# mosfet_board_v2.net
KiCad netlist of a schematic drawn in EAGLE
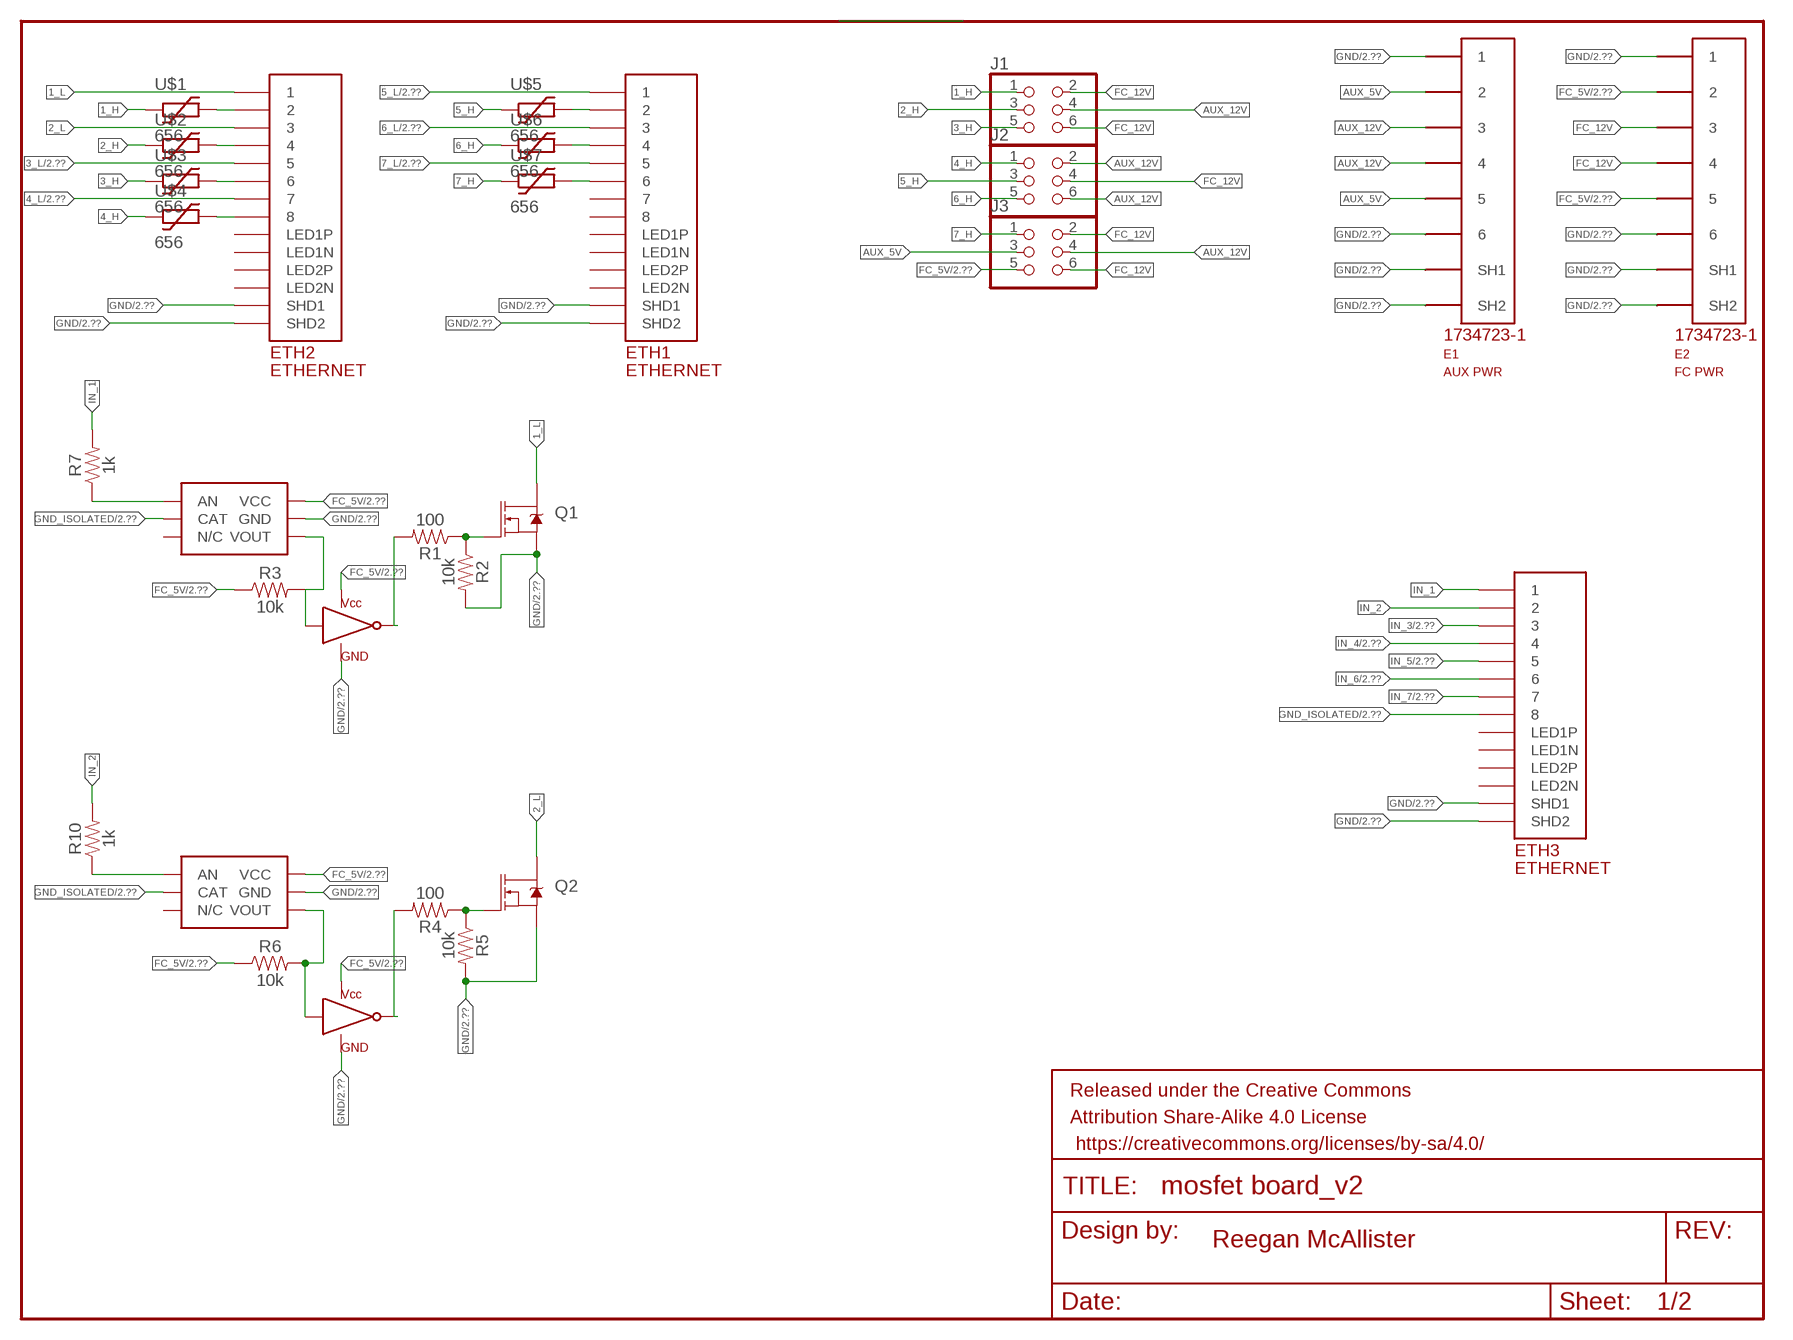
[diagram p0: schematic, sheet 1]
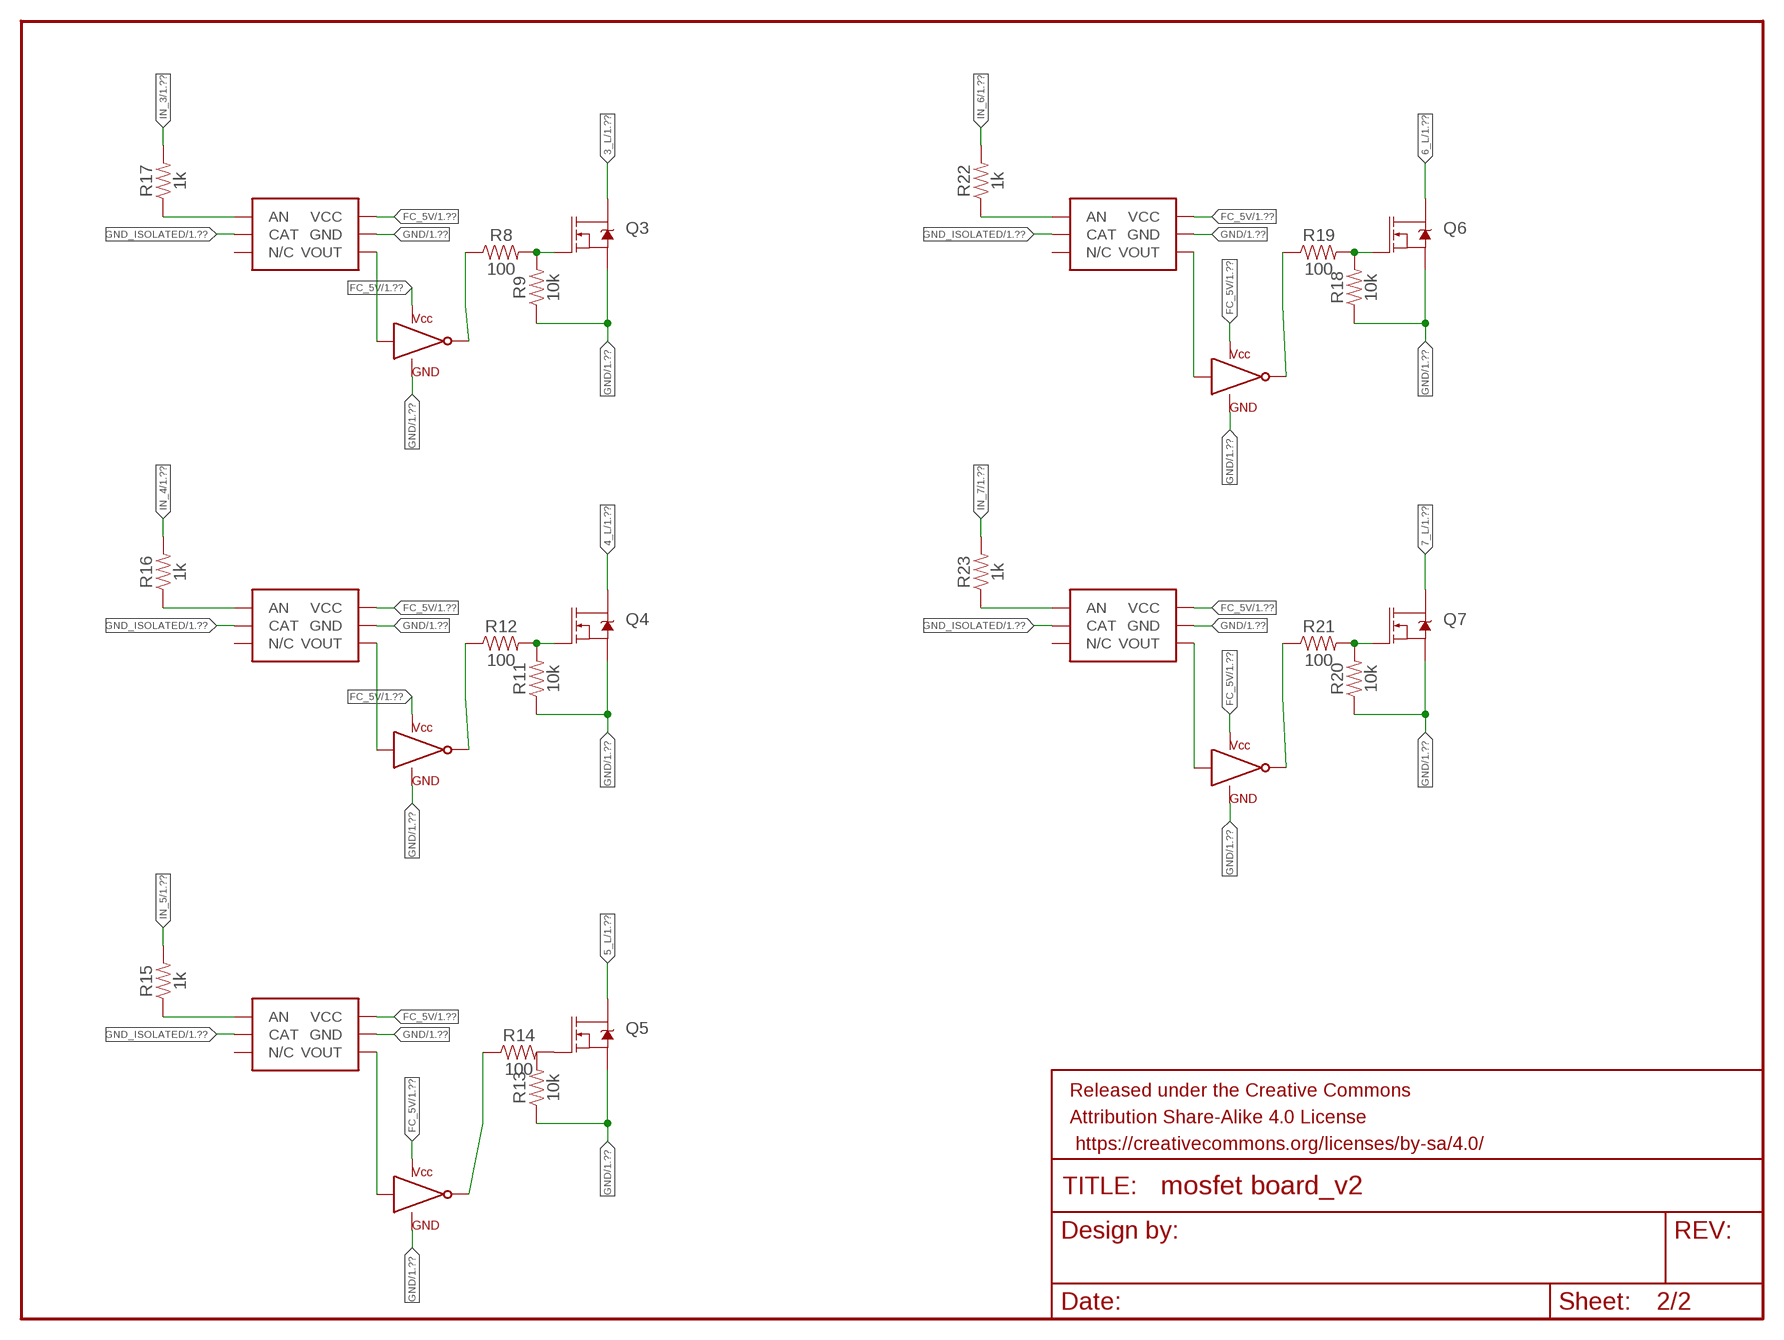
[diagram p1: schematic, sheet 2]

(export (version "E")
  (design (tool "Eeschema 10.0.6"))
  (components
    (comp (ref "E1")
      (value "AUX PWR")
      (footprint "eagle-import:1734723-1_RJ11")
      (libsource (lib "eagle-import") (part "5555140-6"))
    )
    (comp (ref "E2")
      (value "FC PWR")
      (footprint "eagle-import:1734723-1_RJ11")
      (libsource (lib "eagle-import") (part "5555140-6"))
    )
    (comp (ref "ETH1")
      (value "ETHERNET")
      (footprint "eagle-import:A122645-ND")
      (libsource (lib "eagle-import") (part "ETHERNET"))
    )
    (comp (ref "ETH2")
      (value "ETHERNET")
      (footprint "eagle-import:A122645-ND")
      (libsource (lib "eagle-import") (part "ETHERNET"))
    )
    (comp (ref "ETH3")
      (value "ETHERNET")
      (footprint "eagle-import:A122645-ND")
      (libsource (lib "eagle-import") (part "ETHERNET"))
    )
    (comp (ref "FRAME1")
      (value "FRAME-LETTERNO_PACKAGE")
      (footprint "eagle-import:DUMMY")
      (fields (field (name "DESIGNER") "Nobody"))
      (libsource (lib "eagle-import") (part "FRAME-LETTERNO_PACKAGE"))
    )
    (comp (ref "J1")
      (value "PINHD-2X3")
      (footprint "eagle-import:2X03")
      (libsource (lib "eagle-import") (part "PINHD-2X3"))
    )
    (comp (ref "J2")
      (value "PINHD-2X3")
      (footprint "eagle-import:2X03")
      (libsource (lib "eagle-import") (part "PINHD-2X3"))
    )
    (comp (ref "J3")
      (value "PINHD-2X3")
      (footprint "eagle-import:2X03")
      (libsource (lib "eagle-import") (part "PINHD-2X3"))
    )
    (comp (ref "Q1")
      (value "MOSFET-NCH-AO3404A")
      (footprint "eagle-import:SOT23-3")
      (libsource (lib "eagle-import") (part "MOSFET-NCH-AO3404A"))
    )
    (comp (ref "Q2")
      (value "MOSFET-NCH-AO3404A")
      (footprint "eagle-import:SOT23-3")
      (libsource (lib "eagle-import") (part "MOSFET-NCH-AO3404A"))
    )
    (comp (ref "R1")
      (value "100")
      (footprint "eagle-import:0805")
      (libsource (lib "eagle-import") (part "RESISTOR0805"))
    )
    (comp (ref "R2")
      (value "10k")
      (footprint "eagle-import:0805")
      (libsource (lib "eagle-import") (part "RESISTOR0805"))
    )
    (comp (ref "R3")
      (value "10k")
      (footprint "eagle-import:0805")
      (libsource (lib "eagle-import") (part "RESISTOR0805"))
    )
    (comp (ref "R4")
      (value "100")
      (footprint "eagle-import:0805")
      (libsource (lib "eagle-import") (part "RESISTOR0805"))
    )
    (comp (ref "R5")
      (value "10k")
      (footprint "eagle-import:0805")
      (libsource (lib "eagle-import") (part "RESISTOR0805"))
    )
    (comp (ref "R6")
      (value "10k")
      (footprint "eagle-import:0805")
      (libsource (lib "eagle-import") (part "RESISTOR0805"))
    )
    (comp (ref "R7")
      (value "1k")
      (footprint "eagle-import:0805")
      (libsource (lib "eagle-import") (part "RESISTOR0805"))
    )
    (comp (ref "R10")
      (value "1k")
      (footprint "eagle-import:0805")
      (libsource (lib "eagle-import") (part "RESISTOR0805"))
    )
    (comp (ref "U$1")
      (value "656")
      (footprint "eagle-import:656")
      (libsource (lib "eagle-import") (part "656"))
    )
    (comp (ref "U$2")
      (value "656")
      (footprint "eagle-import:656")
      (libsource (lib "eagle-import") (part "656"))
    )
    (comp (ref "U$3")
      (value "656")
      (footprint "eagle-import:656")
      (libsource (lib "eagle-import") (part "656"))
    )
    (comp (ref "U$4")
      (value "656")
      (footprint "eagle-import:656")
      (libsource (lib "eagle-import") (part "656"))
    )
    (comp (ref "U$5")
      (value "656")
      (footprint "eagle-import:656")
      (libsource (lib "eagle-import") (part "656"))
    )
    (comp (ref "U$6")
      (value "656")
      (footprint "eagle-import:656")
      (libsource (lib "eagle-import") (part "656"))
    )
    (comp (ref "U$7")
      (value "656")
      (footprint "eagle-import:656")
      (libsource (lib "eagle-import") (part "656"))
    )
    (comp (ref "U$8")
      (value "H11L1M")
      (footprint "eagle-import:H11L1M")
      (libsource (lib "eagle-import") (part "H11L1M"))
    )
    (comp (ref "U$9")
      (value "SN74LVC1G04-Q1")
      (footprint "eagle-import:SOT-23-5")
      (libsource (lib "eagle-import") (part "SN74LVC1G04-Q1"))
    )
    (comp (ref "U$10")
      (value "H11L1M")
      (footprint "eagle-import:H11L1M")
      (libsource (lib "eagle-import") (part "H11L1M"))
    )
    (comp (ref "U$11")
      (value "SN74LVC1G04-Q1")
      (footprint "eagle-import:SOT-23-5")
      (libsource (lib "eagle-import") (part "SN74LVC1G04-Q1"))
    )
    (comp (ref "FRAME2")
      (value "FRAME-LETTERNO_PACKAGE")
      (footprint "eagle-import:DUMMY")
      (fields (field (name "DESIGNER") "Nobody"))
      (libsource (lib "eagle-import") (part "FRAME-LETTERNO_PACKAGE"))
    )
    (comp (ref "Q3")
      (value "MOSFET-NCH-AO3404A")
      (footprint "eagle-import:SOT23-3")
      (libsource (lib "eagle-import") (part "MOSFET-NCH-AO3404A"))
    )
    (comp (ref "Q4")
      (value "MOSFET-NCH-AO3404A")
      (footprint "eagle-import:SOT23-3")
      (libsource (lib "eagle-import") (part "MOSFET-NCH-AO3404A"))
    )
    (comp (ref "Q5")
      (value "MOSFET-NCH-AO3404A")
      (footprint "eagle-import:SOT23-3")
      (libsource (lib "eagle-import") (part "MOSFET-NCH-AO3404A"))
    )
    (comp (ref "Q6")
      (value "MOSFET-NCH-AO3404A")
      (footprint "eagle-import:SOT23-3")
      (libsource (lib "eagle-import") (part "MOSFET-NCH-AO3404A"))
    )
    (comp (ref "Q7")
      (value "MOSFET-NCH-AO3404A")
      (footprint "eagle-import:SOT23-3")
      (libsource (lib "eagle-import") (part "MOSFET-NCH-AO3404A"))
    )
    (comp (ref "R8")
      (value "100")
      (footprint "eagle-import:0805")
      (libsource (lib "eagle-import") (part "RESISTOR0805"))
    )
    (comp (ref "R9")
      (value "10k")
      (footprint "eagle-import:0805")
      (libsource (lib "eagle-import") (part "RESISTOR0805"))
    )
    (comp (ref "R11")
      (value "10k")
      (footprint "eagle-import:0805")
      (libsource (lib "eagle-import") (part "RESISTOR0805"))
    )
    (comp (ref "R12")
      (value "100")
      (footprint "eagle-import:0805")
      (libsource (lib "eagle-import") (part "RESISTOR0805"))
    )
    (comp (ref "R13")
      (value "10k")
      (footprint "eagle-import:0805")
      (libsource (lib "eagle-import") (part "RESISTOR0805"))
    )
    (comp (ref "R14")
      (value "100")
      (footprint "eagle-import:0805")
      (libsource (lib "eagle-import") (part "RESISTOR0805"))
    )
    (comp (ref "R15")
      (value "1k")
      (footprint "eagle-import:0805")
      (libsource (lib "eagle-import") (part "RESISTOR0805"))
    )
    (comp (ref "R16")
      (value "1k")
      (footprint "eagle-import:0805")
      (libsource (lib "eagle-import") (part "RESISTOR0805"))
    )
    (comp (ref "R17")
      (value "1k")
      (footprint "eagle-import:0805")
      (libsource (lib "eagle-import") (part "RESISTOR0805"))
    )
    (comp (ref "R18")
      (value "10k")
      (footprint "eagle-import:0805")
      (libsource (lib "eagle-import") (part "RESISTOR0805"))
    )
    (comp (ref "R19")
      (value "100")
      (footprint "eagle-import:0805")
      (libsource (lib "eagle-import") (part "RESISTOR0805"))
    )
    (comp (ref "R20")
      (value "10k")
      (footprint "eagle-import:0805")
      (libsource (lib "eagle-import") (part "RESISTOR0805"))
    )
    (comp (ref "R21")
      (value "100")
      (footprint "eagle-import:0805")
      (libsource (lib "eagle-import") (part "RESISTOR0805"))
    )
    (comp (ref "R22")
      (value "1k")
      (footprint "eagle-import:0805")
      (libsource (lib "eagle-import") (part "RESISTOR0805"))
    )
    (comp (ref "R23")
      (value "1k")
      (footprint "eagle-import:0805")
      (libsource (lib "eagle-import") (part "RESISTOR0805"))
    )
    (comp (ref "U$12")
      (value "H11L1M")
      (footprint "eagle-import:H11L1M")
      (libsource (lib "eagle-import") (part "H11L1M"))
    )
    (comp (ref "U$13")
      (value "SN74LVC1G04-Q1")
      (footprint "eagle-import:SOT-23-5")
      (libsource (lib "eagle-import") (part "SN74LVC1G04-Q1"))
    )
    (comp (ref "U$14")
      (value "H11L1M")
      (footprint "eagle-import:H11L1M")
      (libsource (lib "eagle-import") (part "H11L1M"))
    )
    (comp (ref "U$15")
      (value "SN74LVC1G04-Q1")
      (footprint "eagle-import:SOT-23-5")
      (libsource (lib "eagle-import") (part "SN74LVC1G04-Q1"))
    )
    (comp (ref "U$16")
      (value "H11L1M")
      (footprint "eagle-import:H11L1M")
      (libsource (lib "eagle-import") (part "H11L1M"))
    )
    (comp (ref "U$17")
      (value "SN74LVC1G04-Q1")
      (footprint "eagle-import:SOT-23-5")
      (libsource (lib "eagle-import") (part "SN74LVC1G04-Q1"))
    )
    (comp (ref "U$18")
      (value "H11L1M")
      (footprint "eagle-import:H11L1M")
      (libsource (lib "eagle-import") (part "H11L1M"))
    )
    (comp (ref "U$19")
      (value "SN74LVC1G04-Q1")
      (footprint "eagle-import:SOT-23-5")
      (libsource (lib "eagle-import") (part "SN74LVC1G04-Q1"))
    )
    (comp (ref "U$20")
      (value "H11L1M")
      (footprint "eagle-import:H11L1M")
      (libsource (lib "eagle-import") (part "H11L1M"))
    )
    (comp (ref "U$21")
      (value "SN74LVC1G04-Q1")
      (footprint "eagle-import:SOT-23-5")
      (libsource (lib "eagle-import") (part "SN74LVC1G04-Q1"))
    )
  )
  (nets
    (net (code "1") (name "1_H") (class "Default")
      (node (ref "J1") (pin "1") (pinfunction "1_1") (pintype "passive"))
      (node (ref "U$1") (pin "P$1") (pinfunction "1_P$1") (pintype "passive"))
    )
    (net (code "2") (name "1_L") (class "Default")
      (node (ref "ETH2") (pin "P$1") (pinfunction "1_P$1") (pintype "bidirectional"))
      (node (ref "Q1") (pin "3") (pinfunction "D_3") (pintype "bidirectional"))
    )
    (net (code "3") (name "2_H") (class "Default")
      (node (ref "J1") (pin "3") (pinfunction "3_3") (pintype "passive"))
      (node (ref "U$2") (pin "P$1") (pinfunction "1_P$1") (pintype "passive"))
    )
    (net (code "4") (name "2_L") (class "Default")
      (node (ref "ETH2") (pin "P$3") (pinfunction "3_P$3") (pintype "bidirectional"))
      (node (ref "Q2") (pin "3") (pinfunction "D_3") (pintype "bidirectional"))
    )
    (net (code "5") (name "3_H") (class "Default")
      (node (ref "J1") (pin "5") (pinfunction "5_5") (pintype "passive"))
      (node (ref "U$3") (pin "P$1") (pinfunction "1_P$1") (pintype "passive"))
    )
    (net (code "6") (name "3_L") (class "Default")
      (node (ref "ETH2") (pin "P$5") (pinfunction "5_P$5") (pintype "bidirectional"))
      (node (ref "Q3") (pin "3") (pinfunction "D_3") (pintype "bidirectional"))
    )
    (net (code "7") (name "4_H") (class "Default")
      (node (ref "J2") (pin "1") (pinfunction "1_1") (pintype "passive"))
      (node (ref "U$4") (pin "P$1") (pinfunction "1_P$1") (pintype "passive"))
    )
    (net (code "8") (name "4_L") (class "Default")
      (node (ref "ETH2") (pin "P$7") (pinfunction "7_P$7") (pintype "bidirectional"))
      (node (ref "Q4") (pin "3") (pinfunction "D_3") (pintype "bidirectional"))
    )
    (net (code "9") (name "5_H") (class "Default")
      (node (ref "J2") (pin "3") (pinfunction "3_3") (pintype "passive"))
      (node (ref "U$5") (pin "P$1") (pinfunction "1_P$1") (pintype "passive"))
    )
    (net (code "10") (name "5_L") (class "Default")
      (node (ref "ETH1") (pin "P$1") (pinfunction "1_P$1") (pintype "bidirectional"))
      (node (ref "Q5") (pin "3") (pinfunction "D_3") (pintype "bidirectional"))
    )
    (net (code "11") (name "6_H") (class "Default")
      (node (ref "J2") (pin "5") (pinfunction "5_5") (pintype "passive"))
      (node (ref "U$6") (pin "P$1") (pinfunction "1_P$1") (pintype "passive"))
    )
    (net (code "12") (name "6_L") (class "Default")
      (node (ref "ETH1") (pin "P$3") (pinfunction "3_P$3") (pintype "bidirectional"))
      (node (ref "Q6") (pin "3") (pinfunction "D_3") (pintype "bidirectional"))
    )
    (net (code "13") (name "7_H") (class "Default")
      (node (ref "J3") (pin "1") (pinfunction "1_1") (pintype "passive"))
      (node (ref "U$7") (pin "P$1") (pinfunction "1_P$1") (pintype "passive"))
    )
    (net (code "14") (name "7_L") (class "Default")
      (node (ref "ETH1") (pin "P$5") (pinfunction "5_P$5") (pintype "bidirectional"))
      (node (ref "Q7") (pin "3") (pinfunction "D_3") (pintype "bidirectional"))
    )
    (net (code "15") (name "AUX_5V") (class "Default")
      (node (ref "E1") (pin "2") (pinfunction "2_2") (pintype "bidirectional"))
      (node (ref "E1") (pin "5") (pinfunction "5_5") (pintype "bidirectional"))
      (node (ref "J3") (pin "3") (pinfunction "3_3") (pintype "passive"))
    )
    (net (code "16") (name "AUX_12V") (class "Default")
      (node (ref "E1") (pin "3") (pinfunction "3_3") (pintype "bidirectional"))
      (node (ref "E1") (pin "4") (pinfunction "4_4") (pintype "bidirectional"))
      (node (ref "J1") (pin "4") (pinfunction "4_4") (pintype "passive"))
      (node (ref "J2") (pin "2") (pinfunction "2_2") (pintype "passive"))
      (node (ref "J2") (pin "6") (pinfunction "6_6") (pintype "passive"))
      (node (ref "J3") (pin "4") (pinfunction "4_4") (pintype "passive"))
    )
    (net (code "17") (name "FC_5V") (class "Default")
      (node (ref "E2") (pin "2") (pinfunction "2_2") (pintype "bidirectional"))
      (node (ref "E2") (pin "5") (pinfunction "5_5") (pintype "bidirectional"))
      (node (ref "J3") (pin "5") (pinfunction "5_5") (pintype "passive"))
      (node (ref "R3") (pin "1") (pinfunction "1_1") (pintype "passive"))
      (node (ref "R6") (pin "1") (pinfunction "1_1") (pintype "passive"))
      (node (ref "U$10") (pin "P$6") (pinfunction "VCC_P$6") (pintype "bidirectional"))
      (node (ref "U$11") (pin "P$5") (pinfunction "VCC_P$5") (pintype "bidirectional"))
      (node (ref "U$12") (pin "P$6") (pinfunction "VCC_P$6") (pintype "bidirectional"))
      (node (ref "U$13") (pin "P$5") (pinfunction "VCC_P$5") (pintype "bidirectional"))
      (node (ref "U$14") (pin "P$6") (pinfunction "VCC_P$6") (pintype "bidirectional"))
      (node (ref "U$15") (pin "P$5") (pinfunction "VCC_P$5") (pintype "bidirectional"))
      (node (ref "U$16") (pin "P$6") (pinfunction "VCC_P$6") (pintype "bidirectional"))
      (node (ref "U$17") (pin "P$5") (pinfunction "VCC_P$5") (pintype "bidirectional"))
      (node (ref "U$18") (pin "P$6") (pinfunction "VCC_P$6") (pintype "bidirectional"))
      (node (ref "U$19") (pin "P$5") (pinfunction "VCC_P$5") (pintype "bidirectional"))
      (node (ref "U$20") (pin "P$6") (pinfunction "VCC_P$6") (pintype "bidirectional"))
      (node (ref "U$21") (pin "P$5") (pinfunction "VCC_P$5") (pintype "bidirectional"))
      (node (ref "U$8") (pin "P$6") (pinfunction "VCC_P$6") (pintype "bidirectional"))
      (node (ref "U$9") (pin "P$5") (pinfunction "VCC_P$5") (pintype "bidirectional"))
    )
    (net (code "18") (name "FC_12V") (class "Default")
      (node (ref "E2") (pin "3") (pinfunction "3_3") (pintype "bidirectional"))
      (node (ref "E2") (pin "4") (pinfunction "4_4") (pintype "bidirectional"))
      (node (ref "J1") (pin "2") (pinfunction "2_2") (pintype "passive"))
      (node (ref "J1") (pin "6") (pinfunction "6_6") (pintype "passive"))
      (node (ref "J2") (pin "4") (pinfunction "4_4") (pintype "passive"))
      (node (ref "J3") (pin "2") (pinfunction "2_2") (pintype "passive"))
      (node (ref "J3") (pin "6") (pinfunction "6_6") (pintype "passive"))
    )
    (net (code "19") (name "GND") (class "Default")
      (node (ref "E1") (pin "1") (pinfunction "1_1") (pintype "bidirectional"))
      (node (ref "E1") (pin "6") (pinfunction "6_6") (pintype "bidirectional"))
      (node (ref "E1") (pin "SH1") (pinfunction "SH1_SH1") (pintype "bidirectional"))
      (node (ref "E1") (pin "SH2") (pinfunction "SH2_SH2") (pintype "bidirectional"))
      (node (ref "E2") (pin "1") (pinfunction "1_1") (pintype "bidirectional"))
      (node (ref "E2") (pin "6") (pinfunction "6_6") (pintype "bidirectional"))
      (node (ref "E2") (pin "SH1") (pinfunction "SH1_SH1") (pintype "bidirectional"))
      (node (ref "E2") (pin "SH2") (pinfunction "SH2_SH2") (pintype "bidirectional"))
      (node (ref "ETH1") (pin "P$13") (pinfunction "SHD1_P$13") (pintype "bidirectional"))
      (node (ref "ETH1") (pin "P$14") (pinfunction "SHD2_P$14") (pintype "bidirectional"))
      (node (ref "ETH2") (pin "P$13") (pinfunction "SHD1_P$13") (pintype "bidirectional"))
      (node (ref "ETH2") (pin "P$14") (pinfunction "SHD2_P$14") (pintype "bidirectional"))
      (node (ref "ETH3") (pin "P$13") (pinfunction "SHD1_P$13") (pintype "bidirectional"))
      (node (ref "ETH3") (pin "P$14") (pinfunction "SHD2_P$14") (pintype "bidirectional"))
      (node (ref "Q1") (pin "2") (pinfunction "S_2") (pintype "bidirectional"))
      (node (ref "Q2") (pin "2") (pinfunction "S_2") (pintype "bidirectional"))
      (node (ref "Q3") (pin "2") (pinfunction "S_2") (pintype "bidirectional"))
      (node (ref "Q4") (pin "2") (pinfunction "S_2") (pintype "bidirectional"))
      (node (ref "Q5") (pin "2") (pinfunction "S_2") (pintype "bidirectional"))
      (node (ref "Q6") (pin "2") (pinfunction "S_2") (pintype "bidirectional"))
      (node (ref "Q7") (pin "2") (pinfunction "S_2") (pintype "bidirectional"))
      (node (ref "R11") (pin "1") (pinfunction "1_1") (pintype "passive"))
      (node (ref "R13") (pin "1") (pinfunction "1_1") (pintype "passive"))
      (node (ref "R18") (pin "1") (pinfunction "1_1") (pintype "passive"))
      (node (ref "R2") (pin "2") (pinfunction "2_2") (pintype "passive"))
      (node (ref "R20") (pin "1") (pinfunction "1_1") (pintype "passive"))
      (node (ref "R5") (pin "2") (pinfunction "2_2") (pintype "passive"))
      (node (ref "R9") (pin "1") (pinfunction "1_1") (pintype "passive"))
      (node (ref "U$10") (pin "P$5") (pinfunction "GND_P$5") (pintype "bidirectional"))
      (node (ref "U$11") (pin "P$1") (pinfunction "GND_P$1") (pintype "bidirectional"))
      (node (ref "U$11") (pin "P$3") (pinfunction "GND_P$3") (pintype "bidirectional"))
      (node (ref "U$12") (pin "P$5") (pinfunction "GND_P$5") (pintype "bidirectional"))
      (node (ref "U$13") (pin "P$1") (pinfunction "GND_P$1") (pintype "bidirectional"))
      (node (ref "U$13") (pin "P$3") (pinfunction "GND_P$3") (pintype "bidirectional"))
      (node (ref "U$14") (pin "P$5") (pinfunction "GND_P$5") (pintype "bidirectional"))
      (node (ref "U$15") (pin "P$1") (pinfunction "GND_P$1") (pintype "bidirectional"))
      (node (ref "U$15") (pin "P$3") (pinfunction "GND_P$3") (pintype "bidirectional"))
      (node (ref "U$16") (pin "P$5") (pinfunction "GND_P$5") (pintype "bidirectional"))
      (node (ref "U$17") (pin "P$1") (pinfunction "GND_P$1") (pintype "bidirectional"))
      (node (ref "U$17") (pin "P$3") (pinfunction "GND_P$3") (pintype "bidirectional"))
      (node (ref "U$18") (pin "P$5") (pinfunction "GND_P$5") (pintype "bidirectional"))
      (node (ref "U$19") (pin "P$1") (pinfunction "GND_P$1") (pintype "bidirectional"))
      (node (ref "U$19") (pin "P$3") (pinfunction "GND_P$3") (pintype "bidirectional"))
      (node (ref "U$20") (pin "P$5") (pinfunction "GND_P$5") (pintype "bidirectional"))
      (node (ref "U$21") (pin "P$1") (pinfunction "GND_P$1") (pintype "bidirectional"))
      (node (ref "U$21") (pin "P$3") (pinfunction "GND_P$3") (pintype "bidirectional"))
      (node (ref "U$8") (pin "P$5") (pinfunction "GND_P$5") (pintype "bidirectional"))
      (node (ref "U$9") (pin "P$1") (pinfunction "GND_P$1") (pintype "bidirectional"))
      (node (ref "U$9") (pin "P$3") (pinfunction "GND_P$3") (pintype "bidirectional"))
    )
    (net (code "20") (name "GND_ISOLATED") (class "Default")
      (node (ref "ETH3") (pin "P$8") (pinfunction "8_P$8") (pintype "bidirectional"))
      (node (ref "U$10") (pin "P$2") (pinfunction "CAT_P$2") (pintype "bidirectional"))
      (node (ref "U$12") (pin "P$2") (pinfunction "CAT_P$2") (pintype "bidirectional"))
      (node (ref "U$14") (pin "P$2") (pinfunction "CAT_P$2") (pintype "bidirectional"))
      (node (ref "U$16") (pin "P$2") (pinfunction "CAT_P$2") (pintype "bidirectional"))
      (node (ref "U$18") (pin "P$2") (pinfunction "CAT_P$2") (pintype "bidirectional"))
      (node (ref "U$20") (pin "P$2") (pinfunction "CAT_P$2") (pintype "bidirectional"))
      (node (ref "U$8") (pin "P$2") (pinfunction "CAT_P$2") (pintype "bidirectional"))
    )
    (net (code "21") (name "IN_1") (class "Default")
      (node (ref "ETH3") (pin "P$1") (pinfunction "1_P$1") (pintype "bidirectional"))
      (node (ref "R7") (pin "2") (pinfunction "2_2") (pintype "passive"))
    )
    (net (code "22") (name "IN_2") (class "Default")
      (node (ref "ETH3") (pin "P$2") (pinfunction "2_P$2") (pintype "bidirectional"))
      (node (ref "R10") (pin "2") (pinfunction "2_2") (pintype "passive"))
    )
    (net (code "23") (name "IN_3") (class "Default")
      (node (ref "ETH3") (pin "P$3") (pinfunction "3_P$3") (pintype "bidirectional"))
      (node (ref "R17") (pin "2") (pinfunction "2_2") (pintype "passive"))
    )
    (net (code "24") (name "IN_4") (class "Default")
      (node (ref "ETH3") (pin "P$4") (pinfunction "4_P$4") (pintype "bidirectional"))
      (node (ref "R16") (pin "2") (pinfunction "2_2") (pintype "passive"))
    )
    (net (code "25") (name "IN_5") (class "Default")
      (node (ref "ETH3") (pin "P$5") (pinfunction "5_P$5") (pintype "bidirectional"))
      (node (ref "R15") (pin "2") (pinfunction "2_2") (pintype "passive"))
    )
    (net (code "26") (name "IN_6") (class "Default")
      (node (ref "ETH3") (pin "P$6") (pinfunction "6_P$6") (pintype "bidirectional"))
      (node (ref "R22") (pin "2") (pinfunction "2_2") (pintype "passive"))
    )
    (net (code "27") (name "IN_7") (class "Default")
      (node (ref "ETH3") (pin "P$7") (pinfunction "7_P$7") (pintype "bidirectional"))
      (node (ref "R23") (pin "2") (pinfunction "2_2") (pintype "passive"))
    )
    (net (code "28") (name "Net-(ETH1-2)") (class "Default")
      (node (ref "ETH1") (pin "P$2") (pinfunction "2_P$2") (pintype "bidirectional"))
      (node (ref "U$5") (pin "P$2") (pinfunction "2_P$2") (pintype "passive"))
    )
    (net (code "29") (name "Net-(ETH1-4)") (class "Default")
      (node (ref "ETH1") (pin "P$4") (pinfunction "4_P$4") (pintype "bidirectional"))
      (node (ref "U$6") (pin "P$2") (pinfunction "2_P$2") (pintype "passive"))
    )
    (net (code "30") (name "Net-(ETH1-6)") (class "Default")
      (node (ref "ETH1") (pin "P$6") (pinfunction "6_P$6") (pintype "bidirectional"))
      (node (ref "U$7") (pin "P$2") (pinfunction "2_P$2") (pintype "passive"))
    )
    (net (code "31") (name "Net-(ETH2-2)") (class "Default")
      (node (ref "ETH2") (pin "P$2") (pinfunction "2_P$2") (pintype "bidirectional"))
      (node (ref "U$1") (pin "P$2") (pinfunction "2_P$2") (pintype "passive"))
    )
    (net (code "32") (name "Net-(ETH2-4)") (class "Default")
      (node (ref "ETH2") (pin "P$4") (pinfunction "4_P$4") (pintype "bidirectional"))
      (node (ref "U$2") (pin "P$2") (pinfunction "2_P$2") (pintype "passive"))
    )
    (net (code "33") (name "Net-(ETH2-6)") (class "Default")
      (node (ref "ETH2") (pin "P$6") (pinfunction "6_P$6") (pintype "bidirectional"))
      (node (ref "U$3") (pin "P$2") (pinfunction "2_P$2") (pintype "passive"))
    )
    (net (code "34") (name "Net-(ETH2-8)") (class "Default")
      (node (ref "ETH2") (pin "P$8") (pinfunction "8_P$8") (pintype "bidirectional"))
      (node (ref "U$4") (pin "P$2") (pinfunction "2_P$2") (pintype "passive"))
    )
    (net (code "35") (name "Net-(Q1-G)") (class "Default")
      (node (ref "Q1") (pin "1") (pinfunction "G_1") (pintype "bidirectional"))
      (node (ref "R1") (pin "1") (pinfunction "1_1") (pintype "passive"))
      (node (ref "R2") (pin "1") (pinfunction "1_1") (pintype "passive"))
    )
    (net (code "36") (name "Net-(Q2-G)") (class "Default")
      (node (ref "Q2") (pin "1") (pinfunction "G_1") (pintype "bidirectional"))
      (node (ref "R4") (pin "1") (pinfunction "1_1") (pintype "passive"))
      (node (ref "R5") (pin "1") (pinfunction "1_1") (pintype "passive"))
    )
    (net (code "37") (name "Net-(Q3-G)") (class "Default")
      (node (ref "Q3") (pin "1") (pinfunction "G_1") (pintype "bidirectional"))
      (node (ref "R8") (pin "2") (pinfunction "2_2") (pintype "passive"))
      (node (ref "R9") (pin "2") (pinfunction "2_2") (pintype "passive"))
    )
    (net (code "38") (name "Net-(Q4-G)") (class "Default")
      (node (ref "Q4") (pin "1") (pinfunction "G_1") (pintype "bidirectional"))
      (node (ref "R11") (pin "2") (pinfunction "2_2") (pintype "passive"))
      (node (ref "R12") (pin "2") (pinfunction "2_2") (pintype "passive"))
    )
    (net (code "39") (name "Net-(Q5-G)") (class "Default")
      (node (ref "Q5") (pin "1") (pinfunction "G_1") (pintype "bidirectional"))
      (node (ref "R14") (pin "2") (pinfunction "2_2") (pintype "passive"))
    )
    (net (code "40") (name "Net-(Q6-G)") (class "Default")
      (node (ref "Q6") (pin "1") (pinfunction "G_1") (pintype "bidirectional"))
      (node (ref "R18") (pin "2") (pinfunction "2_2") (pintype "passive"))
      (node (ref "R19") (pin "2") (pinfunction "2_2") (pintype "passive"))
    )
    (net (code "41") (name "Net-(Q7-G)") (class "Default")
      (node (ref "Q7") (pin "1") (pinfunction "G_1") (pintype "bidirectional"))
      (node (ref "R20") (pin "2") (pinfunction "2_2") (pintype "passive"))
      (node (ref "R21") (pin "2") (pinfunction "2_2") (pintype "passive"))
    )
    (net (code "42") (name "Net-(U$8-AN)") (class "Default")
      (node (ref "R7") (pin "1") (pinfunction "1_1") (pintype "passive"))
      (node (ref "U$8") (pin "P$1") (pinfunction "AN_P$1") (pintype "bidirectional"))
    )
    (net (code "43") (name "Net-(U$8-VOUT)") (class "Default")
      (node (ref "R3") (pin "2") (pinfunction "2_2") (pintype "passive"))
      (node (ref "U$8") (pin "P$4") (pinfunction "VOUT_P$4") (pintype "bidirectional"))
      (node (ref "U$9") (pin "P$2") (pinfunction "IN_P$2") (pintype "bidirectional"))
    )
    (net (code "44") (name "Net-(U$9-OUT)") (class "Default")
      (node (ref "R1") (pin "2") (pinfunction "2_2") (pintype "passive"))
      (node (ref "U$9") (pin "P$4") (pinfunction "OUT_P$4") (pintype "bidirectional"))
    )
    (net (code "45") (name "Net-(U$10-AN)") (class "Default")
      (node (ref "R10") (pin "1") (pinfunction "1_1") (pintype "passive"))
      (node (ref "U$10") (pin "P$1") (pinfunction "AN_P$1") (pintype "bidirectional"))
    )
    (net (code "46") (name "Net-(U$10-VOUT)") (class "Default")
      (node (ref "R6") (pin "2") (pinfunction "2_2") (pintype "passive"))
      (node (ref "U$10") (pin "P$4") (pinfunction "VOUT_P$4") (pintype "bidirectional"))
      (node (ref "U$11") (pin "P$2") (pinfunction "IN_P$2") (pintype "bidirectional"))
    )
    (net (code "47") (name "Net-(U$11-OUT)") (class "Default")
      (node (ref "R4") (pin "2") (pinfunction "2_2") (pintype "passive"))
      (node (ref "U$11") (pin "P$4") (pinfunction "OUT_P$4") (pintype "bidirectional"))
    )
    (net (code "48") (name "Net-(U$12-AN)") (class "Default")
      (node (ref "R17") (pin "1") (pinfunction "1_1") (pintype "passive"))
      (node (ref "U$12") (pin "P$1") (pinfunction "AN_P$1") (pintype "bidirectional"))
    )
    (net (code "49") (name "Net-(U$12-VOUT)") (class "Default")
      (node (ref "U$12") (pin "P$4") (pinfunction "VOUT_P$4") (pintype "bidirectional"))
      (node (ref "U$13") (pin "P$2") (pinfunction "IN_P$2") (pintype "bidirectional"))
    )
    (net (code "50") (name "Net-(U$13-OUT)") (class "Default")
      (node (ref "R8") (pin "1") (pinfunction "1_1") (pintype "passive"))
      (node (ref "U$13") (pin "P$4") (pinfunction "OUT_P$4") (pintype "bidirectional"))
    )
    (net (code "51") (name "Net-(U$14-AN)") (class "Default")
      (node (ref "R16") (pin "1") (pinfunction "1_1") (pintype "passive"))
      (node (ref "U$14") (pin "P$1") (pinfunction "AN_P$1") (pintype "bidirectional"))
    )
    (net (code "52") (name "Net-(U$14-VOUT)") (class "Default")
      (node (ref "U$14") (pin "P$4") (pinfunction "VOUT_P$4") (pintype "bidirectional"))
      (node (ref "U$15") (pin "P$2") (pinfunction "IN_P$2") (pintype "bidirectional"))
    )
    (net (code "53") (name "Net-(U$15-OUT)") (class "Default")
      (node (ref "R12") (pin "1") (pinfunction "1_1") (pintype "passive"))
      (node (ref "U$15") (pin "P$4") (pinfunction "OUT_P$4") (pintype "bidirectional"))
    )
    (net (code "54") (name "Net-(U$16-AN)") (class "Default")
      (node (ref "R15") (pin "1") (pinfunction "1_1") (pintype "passive"))
      (node (ref "U$16") (pin "P$1") (pinfunction "AN_P$1") (pintype "bidirectional"))
    )
    (net (code "55") (name "Net-(U$16-VOUT)") (class "Default")
      (node (ref "U$16") (pin "P$4") (pinfunction "VOUT_P$4") (pintype "bidirectional"))
      (node (ref "U$17") (pin "P$2") (pinfunction "IN_P$2") (pintype "bidirectional"))
    )
    (net (code "56") (name "Net-(U$17-OUT)") (class "Default")
      (node (ref "R14") (pin "1") (pinfunction "1_1") (pintype "passive"))
      (node (ref "U$17") (pin "P$4") (pinfunction "OUT_P$4") (pintype "bidirectional"))
    )
    (net (code "57") (name "Net-(U$18-AN)") (class "Default")
      (node (ref "R22") (pin "1") (pinfunction "1_1") (pintype "passive"))
      (node (ref "U$18") (pin "P$1") (pinfunction "AN_P$1") (pintype "bidirectional"))
    )
    (net (code "58") (name "Net-(U$18-VOUT)") (class "Default")
      (node (ref "U$18") (pin "P$4") (pinfunction "VOUT_P$4") (pintype "bidirectional"))
      (node (ref "U$19") (pin "P$2") (pinfunction "IN_P$2") (pintype "bidirectional"))
    )
    (net (code "59") (name "Net-(U$19-OUT)") (class "Default")
      (node (ref "R19") (pin "1") (pinfunction "1_1") (pintype "passive"))
      (node (ref "U$19") (pin "P$4") (pinfunction "OUT_P$4") (pintype "bidirectional"))
    )
    (net (code "60") (name "Net-(U$20-AN)") (class "Default")
      (node (ref "R23") (pin "1") (pinfunction "1_1") (pintype "passive"))
      (node (ref "U$20") (pin "P$1") (pinfunction "AN_P$1") (pintype "bidirectional"))
    )
    (net (code "61") (name "Net-(U$20-VOUT)") (class "Default")
      (node (ref "U$20") (pin "P$4") (pinfunction "VOUT_P$4") (pintype "bidirectional"))
      (node (ref "U$21") (pin "P$2") (pinfunction "IN_P$2") (pintype "bidirectional"))
    )
    (net (code "62") (name "Net-(U$21-OUT)") (class "Default")
      (node (ref "R21") (pin "1") (pinfunction "1_1") (pintype "passive"))
      (node (ref "U$21") (pin "P$4") (pinfunction "OUT_P$4") (pintype "bidirectional"))
    )
    (net (code "63") (name "unconnected-(ETH1-7-PadP$7)") (class "Default")
      (node (ref "ETH1") (pin "P$7") (pinfunction "7_P$7") (pintype "bidirectional"))
    )
    (net (code "64") (name "unconnected-(ETH1-8-PadP$8)") (class "Default")
      (node (ref "ETH1") (pin "P$8") (pinfunction "8_P$8") (pintype "bidirectional"))
    )
    (net (code "65") (name "unconnected-(ETH1-LED1N-PadP$9)") (class "Default")
      (node (ref "ETH1") (pin "P$9") (pinfunction "LED1N_P$9") (pintype "bidirectional"))
    )
    (net (code "66") (name "unconnected-(ETH1-LED1P-PadP$10)") (class "Default")
      (node (ref "ETH1") (pin "P$10") (pinfunction "LED1P_P$10") (pintype "bidirectional"))
    )
    (net (code "67") (name "unconnected-(ETH1-LED2N-PadP$11)") (class "Default")
      (node (ref "ETH1") (pin "P$11") (pinfunction "LED2N_P$11") (pintype "bidirectional"))
    )
    (net (code "68") (name "unconnected-(ETH1-LED2P-PadP$12)") (class "Default")
      (node (ref "ETH1") (pin "P$12") (pinfunction "LED2P_P$12") (pintype "bidirectional"))
    )
    (net (code "69") (name "unconnected-(ETH2-LED1N-PadP$9)") (class "Default")
      (node (ref "ETH2") (pin "P$9") (pinfunction "LED1N_P$9") (pintype "bidirectional"))
    )
    (net (code "70") (name "unconnected-(ETH2-LED1P-PadP$10)") (class "Default")
      (node (ref "ETH2") (pin "P$10") (pinfunction "LED1P_P$10") (pintype "bidirectional"))
    )
    (net (code "71") (name "unconnected-(ETH2-LED2N-PadP$11)") (class "Default")
      (node (ref "ETH2") (pin "P$11") (pinfunction "LED2N_P$11") (pintype "bidirectional"))
    )
    (net (code "72") (name "unconnected-(ETH2-LED2P-PadP$12)") (class "Default")
      (node (ref "ETH2") (pin "P$12") (pinfunction "LED2P_P$12") (pintype "bidirectional"))
    )
    (net (code "73") (name "unconnected-(ETH3-LED1N-PadP$9)") (class "Default")
      (node (ref "ETH3") (pin "P$9") (pinfunction "LED1N_P$9") (pintype "bidirectional"))
    )
    (net (code "74") (name "unconnected-(ETH3-LED1P-PadP$10)") (class "Default")
      (node (ref "ETH3") (pin "P$10") (pinfunction "LED1P_P$10") (pintype "bidirectional"))
    )
    (net (code "75") (name "unconnected-(ETH3-LED2N-PadP$11)") (class "Default")
      (node (ref "ETH3") (pin "P$11") (pinfunction "LED2N_P$11") (pintype "bidirectional"))
    )
    (net (code "76") (name "unconnected-(ETH3-LED2P-PadP$12)") (class "Default")
      (node (ref "ETH3") (pin "P$12") (pinfunction "LED2P_P$12") (pintype "bidirectional"))
    )
    (net (code "77") (name "unconnected-(R13-Pad2)") (class "Default")
      (node (ref "R13") (pin "2") (pinfunction "2_2") (pintype "passive"))
    )
    (net (code "78") (name "unconnected-(U$8-N{slash}C-PadP$3)") (class "Default")
      (node (ref "U$8") (pin "P$3") (pinfunction "N/C_P$3") (pintype "bidirectional"))
    )
    (net (code "79") (name "unconnected-(U$10-N{slash}C-PadP$3)") (class "Default")
      (node (ref "U$10") (pin "P$3") (pinfunction "N/C_P$3") (pintype "bidirectional"))
    )
    (net (code "80") (name "unconnected-(U$12-N{slash}C-PadP$3)") (class "Default")
      (node (ref "U$12") (pin "P$3") (pinfunction "N/C_P$3") (pintype "bidirectional"))
    )
    (net (code "81") (name "unconnected-(U$14-N{slash}C-PadP$3)") (class "Default")
      (node (ref "U$14") (pin "P$3") (pinfunction "N/C_P$3") (pintype "bidirectional"))
    )
    (net (code "82") (name "unconnected-(U$16-N{slash}C-PadP$3)") (class "Default")
      (node (ref "U$16") (pin "P$3") (pinfunction "N/C_P$3") (pintype "bidirectional"))
    )
    (net (code "83") (name "unconnected-(U$18-N{slash}C-PadP$3)") (class "Default")
      (node (ref "U$18") (pin "P$3") (pinfunction "N/C_P$3") (pintype "bidirectional"))
    )
    (net (code "84") (name "unconnected-(U$20-N{slash}C-PadP$3)") (class "Default")
      (node (ref "U$20") (pin "P$3") (pinfunction "N/C_P$3") (pintype "bidirectional"))
    )
  )
)
